# Filter_Capacitors_-_Port_K.net
KiCad netlist of a schematic drawn in Altium Designer
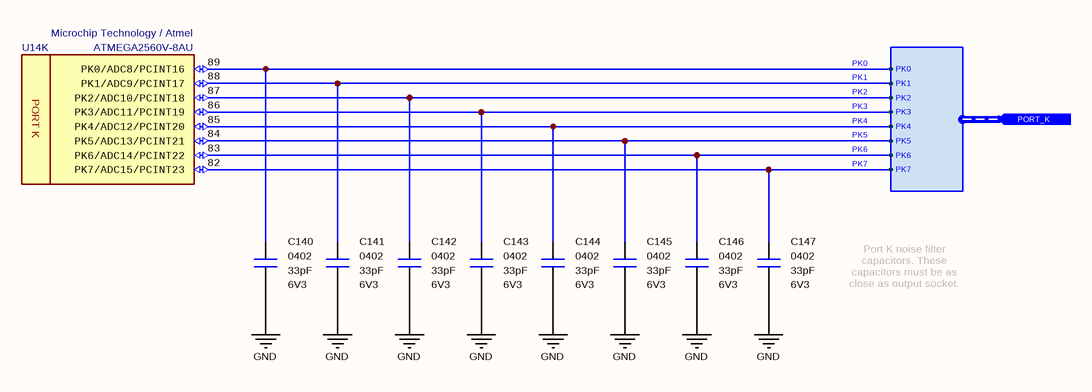
[diagram p0: Filter Capacitors - Port K.SchDoc]

(export (version "E")
  (design (tool "Eeschema 10.0.6"))
  (components
    (comp (ref "C140")
      (value "33pF")
      (footprint "CAPACITOR_0402")
      (description "Capacitor - 33pF [0402] (Ceramic)")
      (fields
        (field (name "TOLERANCE") "10%")
        (field (name "CASE") "0402")
        (field (name "VOLTAGE") "6V3")
        (field (name "MANUFACTURER PART NUMBER") "C0402C330J9RACAUTO")
      )
      (libsource (lib "Ovoo_Library") (part "Capacitor - 33pF [0402-6V3]"))
    )
    (comp (ref "C141")
      (value "33pF")
      (footprint "CAPACITOR_0402")
      (description "Capacitor - 33pF [0402] (Ceramic)")
      (fields
        (field (name "TOLERANCE") "10%")
        (field (name "CASE") "0402")
        (field (name "VOLTAGE") "6V3")
        (field (name "MANUFACTURER PART NUMBER") "C0402C330J9RACAUTO")
      )
      (libsource (lib "Ovoo_Library") (part "Capacitor - 33pF [0402-6V3]"))
    )
    (comp (ref "C142")
      (value "33pF")
      (footprint "CAPACITOR_0402")
      (description "Capacitor - 33pF [0402] (Ceramic)")
      (fields
        (field (name "TOLERANCE") "10%")
        (field (name "CASE") "0402")
        (field (name "VOLTAGE") "6V3")
        (field (name "MANUFACTURER PART NUMBER") "C0402C330J9RACAUTO")
      )
      (libsource (lib "Ovoo_Library") (part "Capacitor - 33pF [0402-6V3]"))
    )
    (comp (ref "C143")
      (value "33pF")
      (footprint "CAPACITOR_0402")
      (description "Capacitor - 33pF [0402] (Ceramic)")
      (fields
        (field (name "TOLERANCE") "10%")
        (field (name "CASE") "0402")
        (field (name "VOLTAGE") "6V3")
        (field (name "MANUFACTURER PART NUMBER") "C0402C330J9RACAUTO")
      )
      (libsource (lib "Ovoo_Library") (part "Capacitor - 33pF [0402-6V3]"))
    )
    (comp (ref "C144")
      (value "33pF")
      (footprint "CAPACITOR_0402")
      (description "Capacitor - 33pF [0402] (Ceramic)")
      (fields
        (field (name "TOLERANCE") "10%")
        (field (name "CASE") "0402")
        (field (name "VOLTAGE") "6V3")
        (field (name "MANUFACTURER PART NUMBER") "C0402C330J9RACAUTO")
      )
      (libsource (lib "Ovoo_Library") (part "Capacitor - 33pF [0402-6V3]"))
    )
    (comp (ref "C145")
      (value "33pF")
      (footprint "CAPACITOR_0402")
      (description "Capacitor - 33pF [0402] (Ceramic)")
      (fields
        (field (name "TOLERANCE") "10%")
        (field (name "CASE") "0402")
        (field (name "VOLTAGE") "6V3")
        (field (name "MANUFACTURER PART NUMBER") "C0402C330J9RACAUTO")
      )
      (libsource (lib "Ovoo_Library") (part "Capacitor - 33pF [0402-6V3]"))
    )
    (comp (ref "C146")
      (value "33pF")
      (footprint "CAPACITOR_0402")
      (description "Capacitor - 33pF [0402] (Ceramic)")
      (fields
        (field (name "TOLERANCE") "10%")
        (field (name "CASE") "0402")
        (field (name "VOLTAGE") "6V3")
        (field (name "MANUFACTURER PART NUMBER") "C0402C330J9RACAUTO")
      )
      (libsource (lib "Ovoo_Library") (part "Capacitor - 33pF [0402-6V3]"))
    )
    (comp (ref "C147")
      (value "33pF")
      (footprint "CAPACITOR_0402")
      (description "Capacitor - 33pF [0402] (Ceramic)")
      (fields
        (field (name "TOLERANCE") "10%")
        (field (name "CASE") "0402")
        (field (name "VOLTAGE") "6V3")
        (field (name "MANUFACTURER PART NUMBER") "C0402C330J9RACAUTO")
      )
      (libsource (lib "Ovoo_Library") (part "Capacitor - 33pF [0402-6V3]"))
    )
    (comp (ref "U14")
      (value "8-bit MicroController")
      (footprint "TQFP100")
      (description "8-bit Microcontrollers - MCU 256kB Flash 4kB EEPROM 86 I/O Pins")
      (fields
        (field (name "MANUFACTURER PART NUMBER") "ATMEGA2560V-8AU")
        (field (name "MANUFACTURER NAME") "Microchip Technology / Atmel")
      )
      (libsource (lib "Ovoo_Library") (part "IC - ATMEGA2560V-8AU"))
    )
  )
  (nets
    (net (code "2") (name "/PK0") (class "Default")
      (node (ref "C140") (pin "2") (pinfunction "2_2") (pintype "passive"))
      (node (ref "U14") (pin "89") (pinfunction "PK0/ADC8/PCINT16_89") (pintype "bidirectional"))
    )
    (net (code "3") (name "/PK1") (class "Default")
      (node (ref "C141") (pin "2") (pinfunction "2_2") (pintype "passive"))
      (node (ref "U14") (pin "88") (pinfunction "PK1/ADC9/PCINT17_88") (pintype "bidirectional"))
    )
    (net (code "4") (name "/PK2") (class "Default")
      (node (ref "C142") (pin "2") (pinfunction "2_2") (pintype "passive"))
      (node (ref "U14") (pin "87") (pinfunction "PK2/ADC10/PCINT18_87") (pintype "bidirectional"))
    )
    (net (code "5") (name "/PK3") (class "Default")
      (node (ref "C143") (pin "2") (pinfunction "2_2") (pintype "passive"))
      (node (ref "U14") (pin "86") (pinfunction "PK3/ADC11/PCINT19_86") (pintype "bidirectional"))
    )
    (net (code "6") (name "/PK4") (class "Default")
      (node (ref "C144") (pin "2") (pinfunction "2_2") (pintype "passive"))
      (node (ref "U14") (pin "85") (pinfunction "PK4/ADC12/PCINT20_85") (pintype "bidirectional"))
    )
    (net (code "7") (name "/PK5") (class "Default")
      (node (ref "C145") (pin "2") (pinfunction "2_2") (pintype "passive"))
      (node (ref "U14") (pin "84") (pinfunction "PK5/ADC13/PCINT21_84") (pintype "bidirectional"))
    )
    (net (code "8") (name "/PK6") (class "Default")
      (node (ref "C146") (pin "2") (pinfunction "2_2") (pintype "passive"))
      (node (ref "U14") (pin "83") (pinfunction "PK6/ADC14/PCINT22_83") (pintype "bidirectional"))
    )
    (net (code "9") (name "/PK7") (class "Default")
      (node (ref "C147") (pin "2") (pinfunction "2_2") (pintype "passive"))
      (node (ref "U14") (pin "82") (pinfunction "PK7/ADC15/PCINT23_82") (pintype "bidirectional"))
    )
    (net (code "11") (name "GND") (class "Default")
      (node (ref "C140") (pin "1") (pinfunction "1_1") (pintype "passive"))
      (node (ref "C141") (pin "1") (pinfunction "1_1") (pintype "passive"))
      (node (ref "C142") (pin "1") (pinfunction "1_1") (pintype "passive"))
      (node (ref "C143") (pin "1") (pinfunction "1_1") (pintype "passive"))
      (node (ref "C144") (pin "1") (pinfunction "1_1") (pintype "passive"))
      (node (ref "C145") (pin "1") (pinfunction "1_1") (pintype "passive"))
      (node (ref "C146") (pin "1") (pinfunction "1_1") (pintype "passive"))
      (node (ref "C147") (pin "1") (pinfunction "1_1") (pintype "passive"))
    )
  )
)
